# pay-ssm.net
KiCad netlist of a schematic drawn in Altium Designer
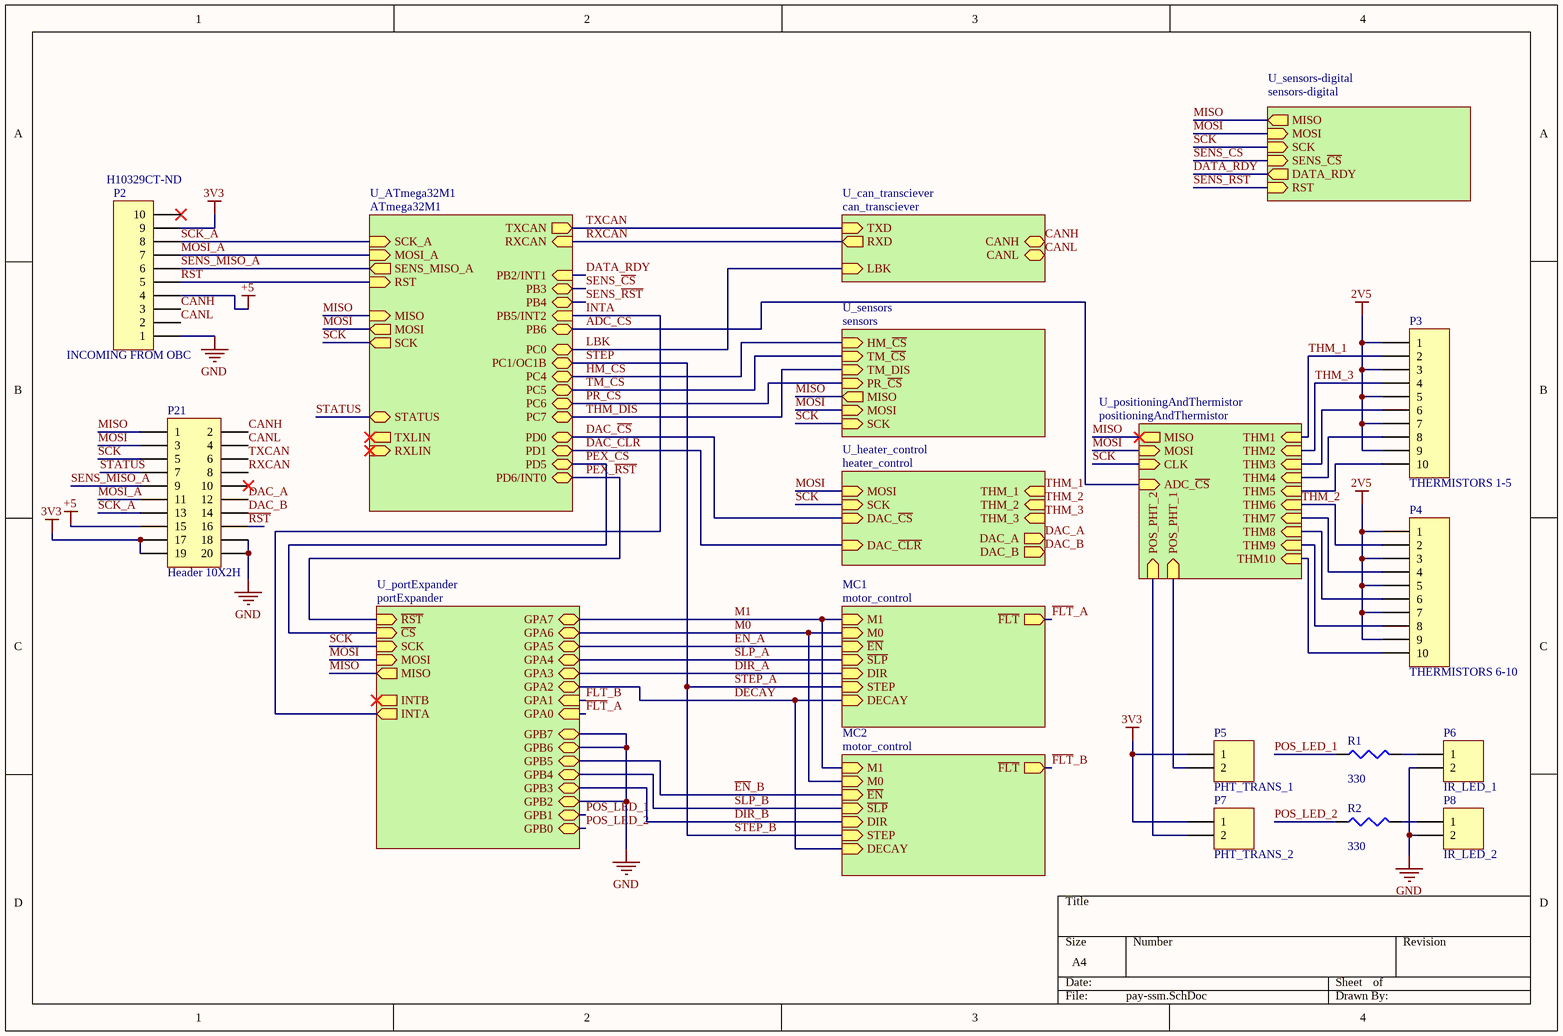
[diagram p0: pay-ssm.SchDoc]

(export (version "E")
  (design (tool "Eeschema 10.0.6"))
  (components
    (comp (ref "P2")
      (value "INCOMING FROM OBC")
      (footprint "DF14-10P-1.25H(55)")
      (description "Header, 10-Pin")
      (fields (field (name "SUPPLIER PART NUMBER") "H10329CT-ND") (field (name "PUBLISHER") "Altium Limited"))
      (libsource (lib "Miscellaneous Connectors") (part "Header 10"))
    )
    (comp (ref "P3")
      (value "THERMISTORS 1-5")
      (footprint "DF14-10P-1.25H(55)")
      (description "Header, 10-Pin")
      (fields (field (name "PUBLISHER") "Altium Limited"))
      (libsource (lib "") (part "Header 10_1"))
    )
    (comp (ref "P4")
      (value "THERMISTORS 6-10")
      (footprint "DF14-10P-1.25H(55)")
      (description "Header, 10-Pin")
      (fields (field (name "PUBLISHER") "Altium Limited"))
      (libsource (lib "") (part "Header 10_1"))
    )
    (comp (ref "P5")
      (value "PHT_TRANS_1")
      (footprint "DF14-2P-1.25H(55)")
      (description "Header, 2-Pin")
      (fields (field (name "PUBLISHER") "Altium Limited"))
      (libsource (lib "Miscellaneous Connectors") (part "Header 2"))
    )
    (comp (ref "P6")
      (value "IR_LED_1")
      (footprint "DF14-2P-1.25H(55)")
      (description "Header, 2-Pin")
      (fields (field (name "PUBLISHER") "Altium Limited"))
      (libsource (lib "Miscellaneous Connectors") (part "Header 2"))
    )
    (comp (ref "P7")
      (value "PHT_TRANS_2")
      (footprint "DF14-2P-1.25H(55)")
      (description "Header, 2-Pin")
      (fields (field (name "PUBLISHER") "Altium Limited"))
      (libsource (lib "Miscellaneous Connectors") (part "Header 2"))
    )
    (comp (ref "P8")
      (value "IR_LED_2")
      (footprint "DF14-2P-1.25H(55)")
      (description "Header, 2-Pin")
      (fields (field (name "PUBLISHER") "Altium Limited"))
      (libsource (lib "Miscellaneous Connectors") (part "Header 2"))
    )
    (comp (ref "P21")
      (value "Header 10X2H")
      (footprint "HDR2X10")
      (description "Header, 10-Pin, Dual row, Right Angle")
      (fields (field (name "PUBLISHER") "Altium Limited"))
      (libsource (lib "Miscellaneous Connectors") (part "Header 10X2H"))
    )
    (comp (ref "R1")
      (value "330")
      (footprint "J1-0603")
      (description "Resistor")
      (fields (field (name "PUBLISHER") "Altium Limited"))
      (libsource (lib "Miscellaneous Devices") (part "Res3"))
    )
    (comp (ref "R2")
      (value "330")
      (footprint "J1-0603")
      (description "Resistor")
      (fields (field (name "PUBLISHER") "Altium Limited"))
      (libsource (lib "Miscellaneous Devices") (part "Res3"))
    )
  )
  (nets
    (net (code "1") (name "+5") (class "Default")
      (node (ref "P2") (pin "4") (pinfunction "4_4") (pintype "passive"))
      (node (ref "P21") (pin "15") (pinfunction "15_15") (pintype "passive"))
    )
    (net (code "3") (name "/CANH") (class "Default")
      (node (ref "P2") (pin "3") (pinfunction "3_3") (pintype "passive"))
      (node (ref "P21") (pin "2") (pinfunction "2_2") (pintype "passive"))
    )
    (net (code "4") (name "/CANL") (class "Default")
      (node (ref "P2") (pin "2") (pinfunction "2_2") (pintype "passive"))
      (node (ref "P21") (pin "4") (pinfunction "4_4") (pintype "passive"))
    )
    (net (code "5") (name "/DAC_A") (class "Default")
      (node (ref "P21") (pin "12") (pinfunction "12_12") (pintype "passive"))
    )
    (net (code "6") (name "/DAC_B") (class "Default")
      (node (ref "P21") (pin "14") (pinfunction "14_14") (pintype "passive"))
    )
    (net (code "19") (name "/MISO") (class "Default")
      (node (ref "P21") (pin "1") (pinfunction "1_1") (pintype "passive"))
    )
    (net (code "20") (name "/MOSI") (class "Default")
      (node (ref "P21") (pin "3") (pinfunction "3_3") (pintype "passive"))
    )
    (net (code "21") (name "/MOSI_A") (class "Default")
      (node (ref "P2") (pin "7") (pinfunction "7_7") (pintype "passive"))
      (node (ref "P21") (pin "11") (pinfunction "11_11") (pintype "passive"))
    )
    (net (code "24") (name "/POS_LED_1") (class "Default")
      (node (ref "R1") (pin "1") (pinfunction "1_1") (pintype "passive"))
    )
    (net (code "25") (name "/POS_LED_2") (class "Default")
      (node (ref "R2") (pin "1") (pinfunction "1_1") (pintype "passive"))
    )
    (net (code "26") (name "/POS_PHT_1") (class "Default")
      (node (ref "P5") (pin "2") (pinfunction "2_2") (pintype "passive"))
    )
    (net (code "27") (name "/POS_PHT_2") (class "Default")
      (node (ref "P7") (pin "2") (pinfunction "2_2") (pintype "passive"))
    )
    (net (code "29") (name "/RXCAN") (class "Default")
      (node (ref "P21") (pin "8") (pinfunction "8_8") (pintype "passive"))
    )
    (net (code "31") (name "/SCK") (class "Default")
      (node (ref "P21") (pin "5") (pinfunction "5_5") (pintype "passive"))
    )
    (net (code "32") (name "/SCK_A") (class "Default")
      (node (ref "P2") (pin "8") (pinfunction "8_8") (pintype "passive"))
      (node (ref "P21") (pin "13") (pinfunction "13_13") (pintype "passive"))
    )
    (net (code "33") (name "/SENS_MISO_A") (class "Default")
      (node (ref "P2") (pin "6") (pinfunction "6_6") (pintype "passive"))
      (node (ref "P21") (pin "9") (pinfunction "9_9") (pintype "passive"))
    )
    (net (code "36") (name "/STATUS") (class "Default")
      (node (ref "P21") (pin "7") (pinfunction "7_7") (pintype "passive"))
    )
    (net (code "38") (name "/THM3") (class "Default")
      (node (ref "P3") (pin "6") (pinfunction "6_6") (pintype "passive"))
    )
    (net (code "39") (name "/THM4") (class "Default")
      (node (ref "P3") (pin "8") (pinfunction "8_8") (pintype "passive"))
    )
    (net (code "40") (name "/THM5") (class "Default")
      (node (ref "P3") (pin "10") (pinfunction "10_10") (pintype "passive"))
    )
    (net (code "41") (name "/THM7") (class "Default")
      (node (ref "P4") (pin "4") (pinfunction "4_4") (pintype "passive"))
    )
    (net (code "42") (name "/THM8") (class "Default")
      (node (ref "P4") (pin "6") (pinfunction "6_6") (pintype "passive"))
    )
    (net (code "43") (name "/THM9") (class "Default")
      (node (ref "P4") (pin "8") (pinfunction "8_8") (pintype "passive"))
    )
    (net (code "44") (name "/THM10") (class "Default")
      (node (ref "P4") (pin "10") (pinfunction "10_10") (pintype "passive"))
    )
    (net (code "45") (name "/THM_1") (class "Default")
      (node (ref "P3") (pin "2") (pinfunction "2_2") (pintype "passive"))
    )
    (net (code "46") (name "/THM_2") (class "Default")
      (node (ref "P4") (pin "2") (pinfunction "2_2") (pintype "passive"))
    )
    (net (code "47") (name "/THM_3") (class "Default")
      (node (ref "P3") (pin "4") (pinfunction "4_4") (pintype "passive"))
    )
    (net (code "50") (name "/TXCAN") (class "Default")
      (node (ref "P21") (pin "6") (pinfunction "6_6") (pintype "passive"))
    )
    (net (code "56") (name "/~{RST}") (class "Default")
      (node (ref "P2") (pin "5") (pinfunction "5_5") (pintype "passive"))
      (node (ref "P21") (pin "16") (pinfunction "16_16") (pintype "passive"))
    )
    (net (code "59") (name "2V5") (class "Default")
      (node (ref "P3") (pin "1") (pinfunction "1_1") (pintype "passive"))
      (node (ref "P3") (pin "3") (pinfunction "3_3") (pintype "passive"))
      (node (ref "P3") (pin "5") (pinfunction "5_5") (pintype "passive"))
      (node (ref "P3") (pin "7") (pinfunction "7_7") (pintype "passive"))
      (node (ref "P3") (pin "9") (pinfunction "9_9") (pintype "passive"))
      (node (ref "P4") (pin "1") (pinfunction "1_1") (pintype "passive"))
      (node (ref "P4") (pin "3") (pinfunction "3_3") (pintype "passive"))
      (node (ref "P4") (pin "5") (pinfunction "5_5") (pintype "passive"))
      (node (ref "P4") (pin "7") (pinfunction "7_7") (pintype "passive"))
      (node (ref "P4") (pin "9") (pinfunction "9_9") (pintype "passive"))
    )
    (net (code "60") (name "3V3") (class "Default")
      (node (ref "P2") (pin "9") (pinfunction "9_9") (pintype "passive"))
      (node (ref "P21") (pin "17") (pinfunction "17_17") (pintype "passive"))
      (node (ref "P21") (pin "19") (pinfunction "19_19") (pintype "passive"))
      (node (ref "P5") (pin "1") (pinfunction "1_1") (pintype "passive"))
      (node (ref "P7") (pin "1") (pinfunction "1_1") (pintype "passive"))
    )
    (net (code "61") (name "GND") (class "Default")
      (node (ref "P2") (pin "1") (pinfunction "1_1") (pintype "passive"))
      (node (ref "P21") (pin "18") (pinfunction "18_18") (pintype "passive"))
      (node (ref "P21") (pin "20") (pinfunction "20_20") (pintype "passive"))
      (node (ref "P6") (pin "2") (pinfunction "2_2") (pintype "passive"))
      (node (ref "P8") (pin "2") (pinfunction "2_2") (pintype "passive"))
    )
    (net (code "62") (name "Net-(P6-Pad1)") (class "Default")
      (node (ref "P6") (pin "1") (pinfunction "1_1") (pintype "passive"))
      (node (ref "R1") (pin "2") (pinfunction "2_2") (pintype "passive"))
    )
    (net (code "63") (name "Net-(P8-Pad1)") (class "Default")
      (node (ref "P8") (pin "1") (pinfunction "1_1") (pintype "passive"))
      (node (ref "R2") (pin "2") (pinfunction "2_2") (pintype "passive"))
    )
    (net (code "64") (name "unconnected-(P2-Pad10)") (class "Default")
      (node (ref "P2") (pin "10") (pinfunction "10_10") (pintype "passive+no_connect"))
    )
    (net (code "65") (name "unconnected-(P21-Pad10)") (class "Default")
      (node (ref "P21") (pin "10") (pinfunction "10_10") (pintype "passive+no_connect"))
    )
  )
)
